# input-sequence.net
KiCad netlist of a schematic drawn in EAGLE
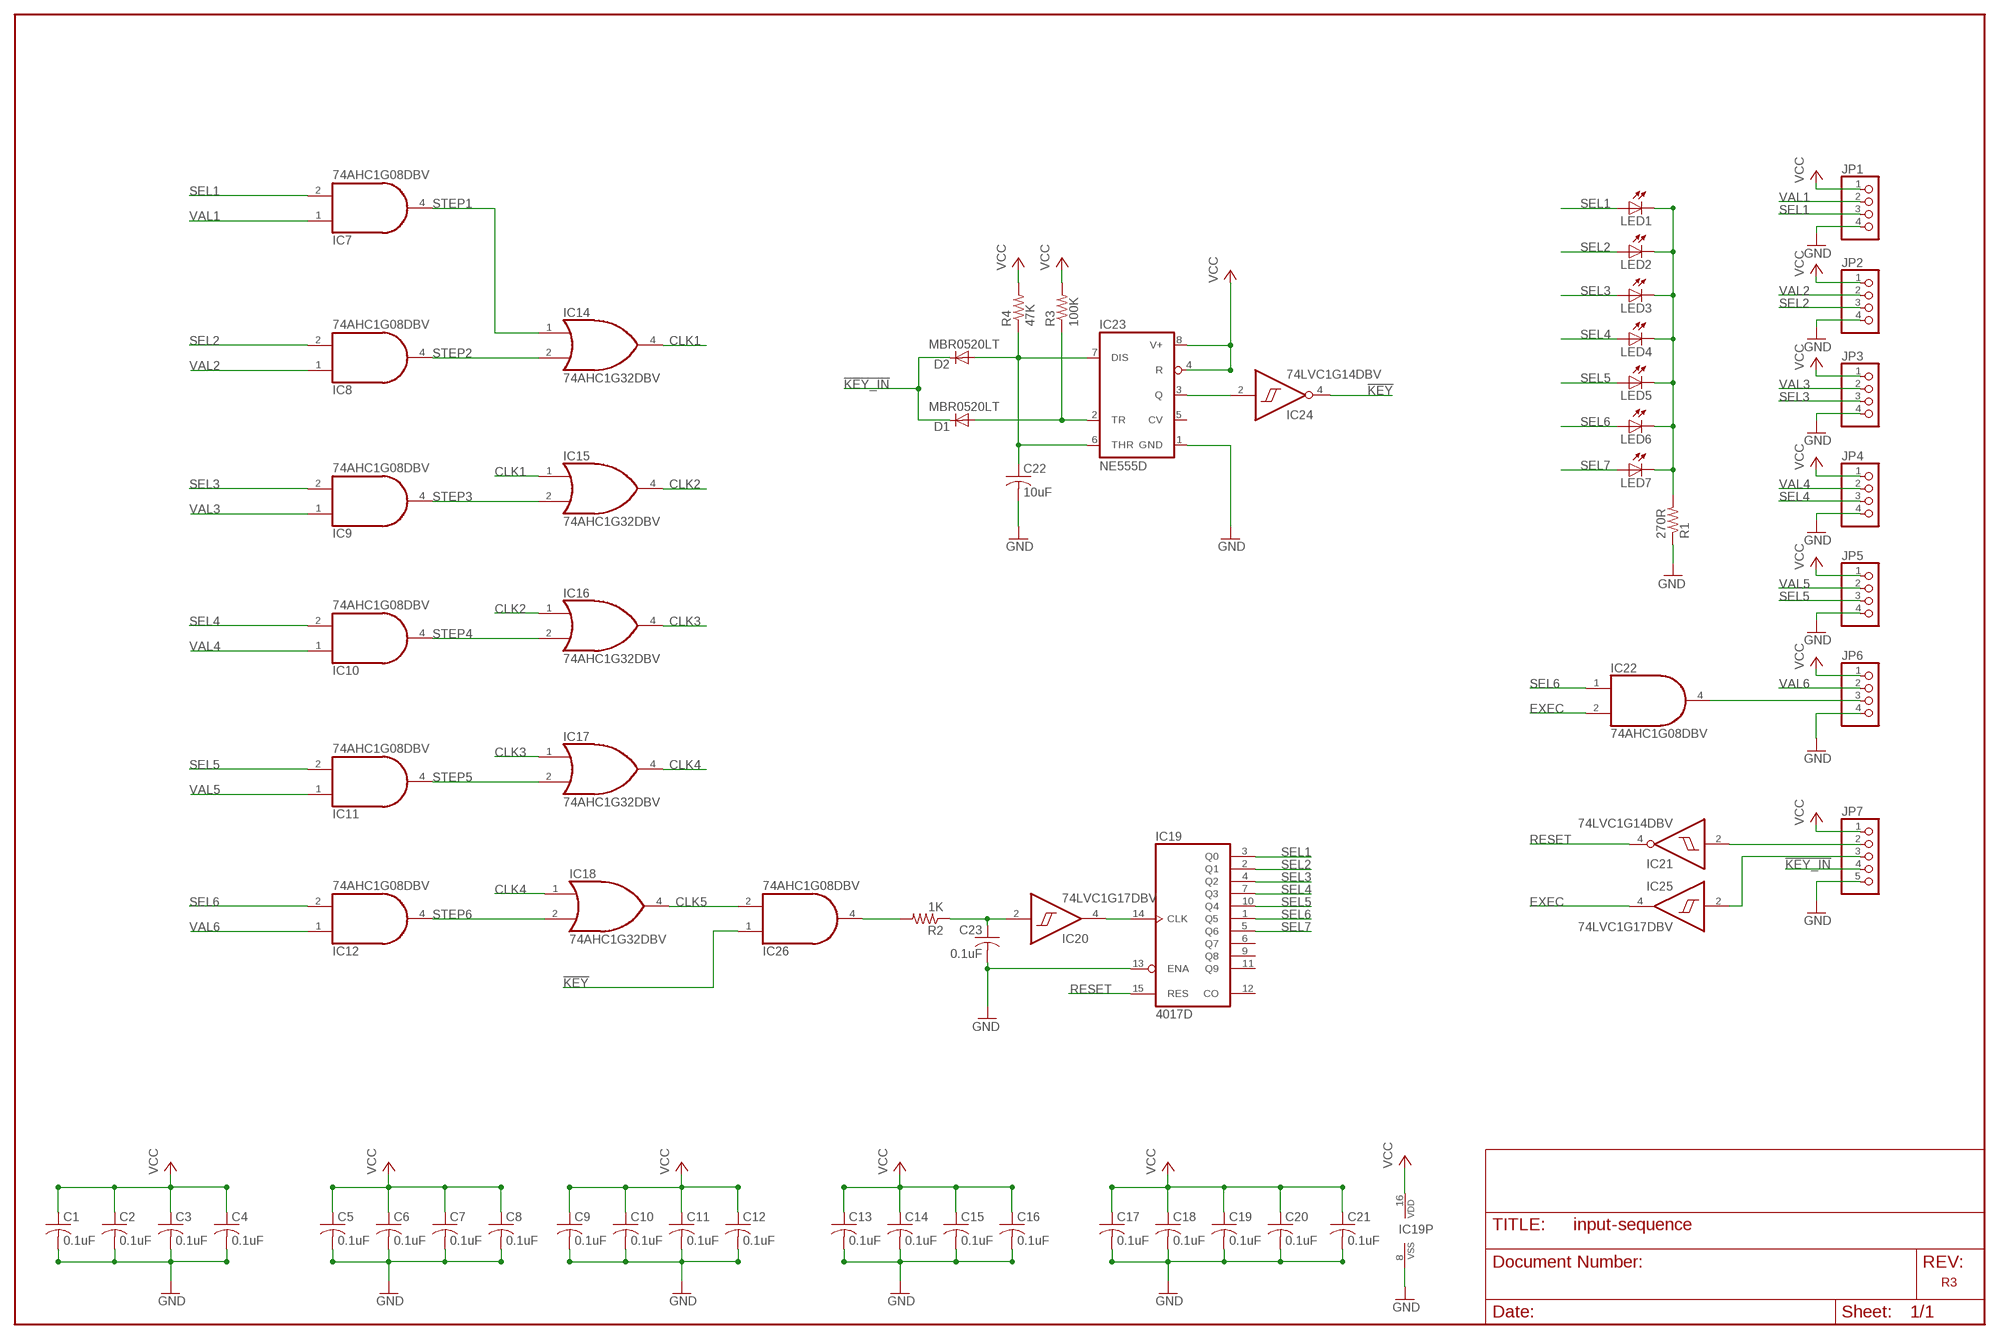
[diagram p0: schematic, sheet 1]

(export (version "E")
  (design (tool "Eeschema 10.0.6"))
  (components
    (comp (ref "C1")
      (value "0.1uF")
      (footprint "eagle-import:C0603")
      (libsource (lib "eagle-import") (part "C-USC0603"))
    )
    (comp (ref "C2")
      (value "0.1uF")
      (footprint "eagle-import:C0603")
      (libsource (lib "eagle-import") (part "C-USC0603"))
    )
    (comp (ref "C3")
      (value "0.1uF")
      (footprint "eagle-import:C0603")
      (libsource (lib "eagle-import") (part "C-USC0603"))
    )
    (comp (ref "C4")
      (value "0.1uF")
      (footprint "eagle-import:C0603")
      (libsource (lib "eagle-import") (part "C-USC0603"))
    )
    (comp (ref "C5")
      (value "0.1uF")
      (footprint "eagle-import:C0603")
      (libsource (lib "eagle-import") (part "C-USC0603"))
    )
    (comp (ref "C6")
      (value "0.1uF")
      (footprint "eagle-import:C0603")
      (libsource (lib "eagle-import") (part "C-USC0603"))
    )
    (comp (ref "C7")
      (value "0.1uF")
      (footprint "eagle-import:C0603")
      (libsource (lib "eagle-import") (part "C-USC0603"))
    )
    (comp (ref "C8")
      (value "0.1uF")
      (footprint "eagle-import:C0603")
      (libsource (lib "eagle-import") (part "C-USC0603"))
    )
    (comp (ref "C9")
      (value "0.1uF")
      (footprint "eagle-import:C0603")
      (libsource (lib "eagle-import") (part "C-USC0603"))
    )
    (comp (ref "C10")
      (value "0.1uF")
      (footprint "eagle-import:C0603")
      (libsource (lib "eagle-import") (part "C-USC0603"))
    )
    (comp (ref "C11")
      (value "0.1uF")
      (footprint "eagle-import:C0603")
      (libsource (lib "eagle-import") (part "C-USC0603"))
    )
    (comp (ref "C12")
      (value "0.1uF")
      (footprint "eagle-import:C0603")
      (libsource (lib "eagle-import") (part "C-USC0603"))
    )
    (comp (ref "C13")
      (value "0.1uF")
      (footprint "eagle-import:C0603")
      (libsource (lib "eagle-import") (part "C-USC0603"))
    )
    (comp (ref "C14")
      (value "0.1uF")
      (footprint "eagle-import:C0603")
      (libsource (lib "eagle-import") (part "C-USC0603"))
    )
    (comp (ref "C15")
      (value "0.1uF")
      (footprint "eagle-import:C0603")
      (libsource (lib "eagle-import") (part "C-USC0603"))
    )
    (comp (ref "C16")
      (value "0.1uF")
      (footprint "eagle-import:C0603")
      (libsource (lib "eagle-import") (part "C-USC0603"))
    )
    (comp (ref "C17")
      (value "0.1uF")
      (footprint "eagle-import:C0603")
      (libsource (lib "eagle-import") (part "C-USC0603"))
    )
    (comp (ref "C18")
      (value "0.1uF")
      (footprint "eagle-import:C0603")
      (libsource (lib "eagle-import") (part "C-USC0603"))
    )
    (comp (ref "C19")
      (value "0.1uF")
      (footprint "eagle-import:C0603")
      (libsource (lib "eagle-import") (part "C-USC0603"))
    )
    (comp (ref "C20")
      (value "0.1uF")
      (footprint "eagle-import:C0603")
      (libsource (lib "eagle-import") (part "C-USC0603"))
    )
    (comp (ref "C21")
      (value "0.1uF")
      (footprint "eagle-import:C0603")
      (libsource (lib "eagle-import") (part "C-USC0603"))
    )
    (comp (ref "C22")
      (value "10uF")
      (footprint "eagle-import:C0805")
      (libsource (lib "eagle-import") (part "C-USC0805"))
    )
    (comp (ref "C23")
      (value "0.1uF")
      (footprint "eagle-import:C0603")
      (libsource (lib "eagle-import") (part "C-USC0603"))
    )
    (comp (ref "D1")
      (value "MBR0520LT")
      (footprint "eagle-import:SOD123")
      (libsource (lib "eagle-import") (part "MBR0520LT"))
    )
    (comp (ref "D2")
      (value "MBR0520LT")
      (footprint "eagle-import:SOD123")
      (libsource (lib "eagle-import") (part "MBR0520LT"))
    )
    (comp (ref "IC7")
      (value "74AHC1G08DBV")
      (footprint "eagle-import:SOT23-5")
      (libsource (lib "eagle-import") (part "741G08DBVAHC"))
    )
    (comp (ref "IC8")
      (value "74AHC1G08DBV")
      (footprint "eagle-import:SOT23-5")
      (libsource (lib "eagle-import") (part "741G08DBVAHC"))
    )
    (comp (ref "IC9")
      (value "74AHC1G08DBV")
      (footprint "eagle-import:SOT23-5")
      (libsource (lib "eagle-import") (part "741G08DBVAHC"))
    )
    (comp (ref "IC10")
      (value "74AHC1G08DBV")
      (footprint "eagle-import:SOT23-5")
      (libsource (lib "eagle-import") (part "741G08DBVAHC"))
    )
    (comp (ref "IC11")
      (value "74AHC1G08DBV")
      (footprint "eagle-import:SOT23-5")
      (libsource (lib "eagle-import") (part "741G08DBVAHC"))
    )
    (comp (ref "IC12")
      (value "74AHC1G08DBV")
      (footprint "eagle-import:SOT23-5")
      (libsource (lib "eagle-import") (part "741G08DBVAHC"))
    )
    (comp (ref "IC14")
      (value "74AHC1G32DBV")
      (footprint "eagle-import:SOT23-5")
      (libsource (lib "eagle-import") (part "741G32DBVAHC"))
    )
    (comp (ref "IC15")
      (value "74AHC1G32DBV")
      (footprint "eagle-import:SOT23-5")
      (libsource (lib "eagle-import") (part "741G32DBVAHC"))
    )
    (comp (ref "IC16")
      (value "74AHC1G32DBV")
      (footprint "eagle-import:SOT23-5")
      (libsource (lib "eagle-import") (part "741G32DBVAHC"))
    )
    (comp (ref "IC17")
      (value "74AHC1G32DBV")
      (footprint "eagle-import:SOT23-5")
      (libsource (lib "eagle-import") (part "741G32DBVAHC"))
    )
    (comp (ref "IC18")
      (value "74AHC1G32DBV")
      (footprint "eagle-import:SOT23-5")
      (libsource (lib "eagle-import") (part "741G32DBVAHC"))
    )
    (comp (ref "IC19")
      (value "4017D")
      (footprint "eagle-import:SO16")
      (libsource (lib "eagle-import") (part "4017D"))
    )
    (comp (ref "IC20")
      (value "74LVC1G17DBV")
      (footprint "eagle-import:SOT23-5")
      (libsource (lib "eagle-import") (part "741G17DBVLVC"))
    )
    (comp (ref "IC21")
      (value "74LVC1G14DBV")
      (footprint "eagle-import:SOT23-5")
      (libsource (lib "eagle-import") (part "741G14DBVLVC"))
    )
    (comp (ref "IC22")
      (value "74AHC1G08DBV")
      (footprint "eagle-import:SOT23-5")
      (libsource (lib "eagle-import") (part "741G08DBVAHC"))
    )
    (comp (ref "IC23")
      (value "NE555D")
      (footprint "eagle-import:SO08")
      (libsource (lib "eagle-import") (part "555DNE"))
    )
    (comp (ref "IC24")
      (value "74LVC1G14DBV")
      (footprint "eagle-import:SOT23-5")
      (libsource (lib "eagle-import") (part "741G14DBVLVC"))
    )
    (comp (ref "IC25")
      (value "74LVC1G17DBV")
      (footprint "eagle-import:SOT23-5")
      (libsource (lib "eagle-import") (part "741G17DBVLVC"))
    )
    (comp (ref "IC26")
      (value "74AHC1G08DBV")
      (footprint "eagle-import:SOT23-5")
      (libsource (lib "eagle-import") (part "741G08DBVAHC"))
    )
    (comp (ref "JP1")
      (value "PINHD-1X4")
      (footprint "eagle-import:1X04")
      (libsource (lib "eagle-import") (part "PINHD-1X4"))
    )
    (comp (ref "JP2")
      (value "PINHD-1X4")
      (footprint "eagle-import:1X04")
      (libsource (lib "eagle-import") (part "PINHD-1X4"))
    )
    (comp (ref "JP3")
      (value "PINHD-1X4")
      (footprint "eagle-import:1X04")
      (libsource (lib "eagle-import") (part "PINHD-1X4"))
    )
    (comp (ref "JP4")
      (value "PINHD-1X4")
      (footprint "eagle-import:1X04")
      (libsource (lib "eagle-import") (part "PINHD-1X4"))
    )
    (comp (ref "JP5")
      (value "PINHD-1X4")
      (footprint "eagle-import:1X04")
      (libsource (lib "eagle-import") (part "PINHD-1X4"))
    )
    (comp (ref "JP6")
      (value "PINHD-1X4")
      (footprint "eagle-import:1X04")
      (libsource (lib "eagle-import") (part "PINHD-1X4"))
    )
    (comp (ref "JP7")
      (value "PINHD-1X5")
      (footprint "eagle-import:1X05")
      (libsource (lib "eagle-import") (part "PINHD-1X5"))
    )
    (comp (ref "LED1")
      (value "RED")
      (footprint "eagle-import:CHIP-LED0805")
      (libsource (lib "eagle-import") (part "LEDCHIP-LED0805"))
    )
    (comp (ref "LED2")
      (value "RED")
      (footprint "eagle-import:CHIP-LED0805")
      (libsource (lib "eagle-import") (part "LEDCHIP-LED0805"))
    )
    (comp (ref "LED3")
      (value "RED")
      (footprint "eagle-import:CHIP-LED0805")
      (libsource (lib "eagle-import") (part "LEDCHIP-LED0805"))
    )
    (comp (ref "LED4")
      (value "RED")
      (footprint "eagle-import:CHIP-LED0805")
      (libsource (lib "eagle-import") (part "LEDCHIP-LED0805"))
    )
    (comp (ref "LED5")
      (value "RED")
      (footprint "eagle-import:CHIP-LED0805")
      (libsource (lib "eagle-import") (part "LEDCHIP-LED0805"))
    )
    (comp (ref "LED6")
      (value "RED")
      (footprint "eagle-import:CHIP-LED0805")
      (libsource (lib "eagle-import") (part "LEDCHIP-LED0805"))
    )
    (comp (ref "LED7")
      (value "RED")
      (footprint "eagle-import:CHIP-LED0805")
      (libsource (lib "eagle-import") (part "LEDCHIP-LED0805"))
    )
    (comp (ref "R1")
      (value "270R")
      (footprint "eagle-import:R0805")
      (libsource (lib "eagle-import") (part "R-US_R0805"))
    )
    (comp (ref "R2")
      (value "1K")
      (footprint "eagle-import:R0805")
      (libsource (lib "eagle-import") (part "R-US_R0805"))
    )
    (comp (ref "R3")
      (value "100K")
      (footprint "eagle-import:R0805")
      (libsource (lib "eagle-import") (part "R-US_R0805"))
    )
    (comp (ref "R4")
      (value "47K")
      (footprint "eagle-import:R0805")
      (libsource (lib "eagle-import") (part "R-US_R0805"))
    )
  )
  (nets
    (net (code "1") (name "/CLK1") (class "Default")
      (node (ref "IC14") (pin "4") (pinfunction "O_4") (pintype "output"))
      (node (ref "IC15") (pin "1") (pinfunction "I0_1") (pintype "input"))
    )
    (net (code "2") (name "/CLK2") (class "Default")
      (node (ref "IC15") (pin "4") (pinfunction "O_4") (pintype "output"))
      (node (ref "IC16") (pin "1") (pinfunction "I0_1") (pintype "input"))
    )
    (net (code "3") (name "/CLK3") (class "Default")
      (node (ref "IC16") (pin "4") (pinfunction "O_4") (pintype "output"))
      (node (ref "IC17") (pin "1") (pinfunction "I0_1") (pintype "input"))
    )
    (net (code "4") (name "/CLK4") (class "Default")
      (node (ref "IC17") (pin "4") (pinfunction "O_4") (pintype "output"))
      (node (ref "IC18") (pin "1") (pinfunction "I0_1") (pintype "input"))
    )
    (net (code "5") (name "/CLK5") (class "Default")
      (node (ref "IC18") (pin "4") (pinfunction "O_4") (pintype "output"))
      (node (ref "IC26") (pin "2") (pinfunction "I1_2") (pintype "input"))
    )
    (net (code "6") (name "/EXEC") (class "Default")
      (node (ref "IC22") (pin "2") (pinfunction "I1_2") (pintype "input"))
      (node (ref "IC25") (pin "4") (pinfunction "O_4") (pintype "output"))
    )
    (net (code "7") (name "/RESET") (class "Default")
      (node (ref "IC19") (pin "15") (pinfunction "RES_15") (pintype "input"))
      (node (ref "IC21") (pin "4") (pinfunction "O_4") (pintype "output"))
    )
    (net (code "8") (name "/SEL1") (class "Default")
      (node (ref "IC19") (pin "3") (pinfunction "Q0_3") (pintype "output"))
      (node (ref "IC7") (pin "2") (pinfunction "I1_2") (pintype "input"))
      (node (ref "JP1") (pin "3") (pinfunction "3_3") (pintype "passive"))
      (node (ref "LED1") (pin "A") (pinfunction "A_A") (pintype "passive"))
    )
    (net (code "9") (name "/SEL2") (class "Default")
      (node (ref "IC19") (pin "2") (pinfunction "Q1_2") (pintype "output"))
      (node (ref "IC8") (pin "2") (pinfunction "I1_2") (pintype "input"))
      (node (ref "JP2") (pin "3") (pinfunction "3_3") (pintype "passive"))
      (node (ref "LED2") (pin "A") (pinfunction "A_A") (pintype "passive"))
    )
    (net (code "10") (name "/SEL3") (class "Default")
      (node (ref "IC19") (pin "4") (pinfunction "Q2_4") (pintype "output"))
      (node (ref "IC9") (pin "2") (pinfunction "I1_2") (pintype "input"))
      (node (ref "JP3") (pin "3") (pinfunction "3_3") (pintype "passive"))
      (node (ref "LED3") (pin "A") (pinfunction "A_A") (pintype "passive"))
    )
    (net (code "11") (name "/SEL4") (class "Default")
      (node (ref "IC10") (pin "2") (pinfunction "I1_2") (pintype "input"))
      (node (ref "IC19") (pin "7") (pinfunction "Q3_7") (pintype "output"))
      (node (ref "JP4") (pin "3") (pinfunction "3_3") (pintype "passive"))
      (node (ref "LED4") (pin "A") (pinfunction "A_A") (pintype "passive"))
    )
    (net (code "12") (name "/SEL5") (class "Default")
      (node (ref "IC11") (pin "2") (pinfunction "I1_2") (pintype "input"))
      (node (ref "IC19") (pin "10") (pinfunction "Q4_10") (pintype "output"))
      (node (ref "JP5") (pin "3") (pinfunction "3_3") (pintype "passive"))
      (node (ref "LED5") (pin "A") (pinfunction "A_A") (pintype "passive"))
    )
    (net (code "13") (name "/SEL6") (class "Default")
      (node (ref "IC12") (pin "2") (pinfunction "I1_2") (pintype "input"))
      (node (ref "IC19") (pin "1") (pinfunction "Q5_1") (pintype "output"))
      (node (ref "IC22") (pin "1") (pinfunction "I0_1") (pintype "input"))
      (node (ref "LED6") (pin "A") (pinfunction "A_A") (pintype "passive"))
    )
    (net (code "14") (name "/SEL7") (class "Default")
      (node (ref "IC19") (pin "5") (pinfunction "Q6_5") (pintype "output"))
      (node (ref "LED7") (pin "A") (pinfunction "A_A") (pintype "passive"))
    )
    (net (code "15") (name "/STEP1") (class "Default")
      (node (ref "IC14") (pin "1") (pinfunction "I0_1") (pintype "input"))
      (node (ref "IC7") (pin "4") (pinfunction "O_4") (pintype "output"))
    )
    (net (code "16") (name "/STEP2") (class "Default")
      (node (ref "IC14") (pin "2") (pinfunction "I1_2") (pintype "input"))
      (node (ref "IC8") (pin "4") (pinfunction "O_4") (pintype "output"))
    )
    (net (code "17") (name "/STEP3") (class "Default")
      (node (ref "IC15") (pin "2") (pinfunction "I1_2") (pintype "input"))
      (node (ref "IC9") (pin "4") (pinfunction "O_4") (pintype "output"))
    )
    (net (code "18") (name "/STEP4") (class "Default")
      (node (ref "IC10") (pin "4") (pinfunction "O_4") (pintype "output"))
      (node (ref "IC16") (pin "2") (pinfunction "I1_2") (pintype "input"))
    )
    (net (code "19") (name "/STEP5") (class "Default")
      (node (ref "IC11") (pin "4") (pinfunction "O_4") (pintype "output"))
      (node (ref "IC17") (pin "2") (pinfunction "I1_2") (pintype "input"))
    )
    (net (code "20") (name "/STEP6") (class "Default")
      (node (ref "IC12") (pin "4") (pinfunction "O_4") (pintype "output"))
      (node (ref "IC18") (pin "2") (pinfunction "I1_2") (pintype "input"))
    )
    (net (code "21") (name "/VAL1") (class "Default")
      (node (ref "IC7") (pin "1") (pinfunction "I0_1") (pintype "input"))
      (node (ref "JP1") (pin "2") (pinfunction "2_2") (pintype "passive"))
    )
    (net (code "22") (name "/VAL2") (class "Default")
      (node (ref "IC8") (pin "1") (pinfunction "I0_1") (pintype "input"))
      (node (ref "JP2") (pin "2") (pinfunction "2_2") (pintype "passive"))
    )
    (net (code "23") (name "/VAL3") (class "Default")
      (node (ref "IC9") (pin "1") (pinfunction "I0_1") (pintype "input"))
      (node (ref "JP3") (pin "2") (pinfunction "2_2") (pintype "passive"))
    )
    (net (code "24") (name "/VAL4") (class "Default")
      (node (ref "IC10") (pin "1") (pinfunction "I0_1") (pintype "input"))
      (node (ref "JP4") (pin "2") (pinfunction "2_2") (pintype "passive"))
    )
    (net (code "25") (name "/VAL5") (class "Default")
      (node (ref "IC11") (pin "1") (pinfunction "I0_1") (pintype "input"))
      (node (ref "JP5") (pin "2") (pinfunction "2_2") (pintype "passive"))
    )
    (net (code "26") (name "/VAL6") (class "Default")
      (node (ref "IC12") (pin "1") (pinfunction "I0_1") (pintype "input"))
      (node (ref "JP6") (pin "2") (pinfunction "2_2") (pintype "passive"))
    )
    (net (code "27") (name "/~{KEY_IN}") (class "Default")
      (node (ref "D1") (pin "C") (pinfunction "C_C") (pintype "passive"))
      (node (ref "D2") (pin "C") (pinfunction "C_C") (pintype "passive"))
      (node (ref "JP7") (pin "4") (pinfunction "4_4") (pintype "passive"))
    )
    (net (code "28") (name "/~{KEY}") (class "Default")
      (node (ref "IC24") (pin "4") (pinfunction "O_4") (pintype "output"))
      (node (ref "IC26") (pin "1") (pinfunction "I0_1") (pintype "input"))
    )
    (net (code "29") (name "GND") (class "Default")
      (node (ref "C1") (pin "2") (pinfunction "2_2") (pintype "passive"))
      (node (ref "C10") (pin "2") (pinfunction "2_2") (pintype "passive"))
      (node (ref "C11") (pin "2") (pinfunction "2_2") (pintype "passive"))
      (node (ref "C12") (pin "2") (pinfunction "2_2") (pintype "passive"))
      (node (ref "C13") (pin "2") (pinfunction "2_2") (pintype "passive"))
      (node (ref "C14") (pin "2") (pinfunction "2_2") (pintype "passive"))
      (node (ref "C15") (pin "2") (pinfunction "2_2") (pintype "passive"))
      (node (ref "C16") (pin "2") (pinfunction "2_2") (pintype "passive"))
      (node (ref "C17") (pin "2") (pinfunction "2_2") (pintype "passive"))
      (node (ref "C18") (pin "2") (pinfunction "2_2") (pintype "passive"))
      (node (ref "C19") (pin "2") (pinfunction "2_2") (pintype "passive"))
      (node (ref "C2") (pin "2") (pinfunction "2_2") (pintype "passive"))
      (node (ref "C20") (pin "2") (pinfunction "2_2") (pintype "passive"))
      (node (ref "C21") (pin "2") (pinfunction "2_2") (pintype "passive"))
      (node (ref "C22") (pin "2") (pinfunction "2_2") (pintype "passive"))
      (node (ref "C23") (pin "2") (pinfunction "2_2") (pintype "passive"))
      (node (ref "C3") (pin "2") (pinfunction "2_2") (pintype "passive"))
      (node (ref "C4") (pin "2") (pinfunction "2_2") (pintype "passive"))
      (node (ref "C5") (pin "2") (pinfunction "2_2") (pintype "passive"))
      (node (ref "C6") (pin "2") (pinfunction "2_2") (pintype "passive"))
      (node (ref "C7") (pin "2") (pinfunction "2_2") (pintype "passive"))
      (node (ref "C8") (pin "2") (pinfunction "2_2") (pintype "passive"))
      (node (ref "C9") (pin "2") (pinfunction "2_2") (pintype "passive"))
      (node (ref "IC19") (pin "13") (pinfunction "ENA_13") (pintype "input"))
      (node (ref "IC19") (pin "8") (pinfunction "VSS_8") (pintype "power_in"))
      (node (ref "IC23") (pin "1") (pinfunction "GND_1") (pintype "power_in"))
      (node (ref "JP1") (pin "4") (pinfunction "4_4") (pintype "passive"))
      (node (ref "JP2") (pin "4") (pinfunction "4_4") (pintype "passive"))
      (node (ref "JP3") (pin "4") (pinfunction "4_4") (pintype "passive"))
      (node (ref "JP4") (pin "4") (pinfunction "4_4") (pintype "passive"))
      (node (ref "JP5") (pin "4") (pinfunction "4_4") (pintype "passive"))
      (node (ref "JP6") (pin "4") (pinfunction "4_4") (pintype "passive"))
      (node (ref "JP7") (pin "5") (pinfunction "5_5") (pintype "passive"))
      (node (ref "R1") (pin "1") (pinfunction "1_1") (pintype "passive"))
    )
    (net (code "30") (name "Net-(IC19A-CLK)") (class "Default")
      (node (ref "IC19") (pin "14") (pinfunction "CLK_14") (pintype "input"))
      (node (ref "IC20") (pin "4") (pinfunction "O_4") (pintype "output"))
    )
    (net (code "31") (name "Net-(IC20A-I)") (class "Default")
      (node (ref "C23") (pin "1") (pinfunction "1_1") (pintype "passive"))
      (node (ref "IC20") (pin "2") (pinfunction "I_2") (pintype "input"))
      (node (ref "R2") (pin "1") (pinfunction "1_1") (pintype "passive"))
    )
    (net (code "32") (name "Net-(IC21A-I)") (class "Default")
      (node (ref "IC21") (pin "2") (pinfunction "I_2") (pintype "input"))
      (node (ref "JP7") (pin "2") (pinfunction "2_2") (pintype "passive"))
    )
    (net (code "33") (name "Net-(IC22A-O)") (class "Default")
      (node (ref "IC22") (pin "4") (pinfunction "O_4") (pintype "output"))
      (node (ref "JP6") (pin "3") (pinfunction "3_3") (pintype "passive"))
    )
    (net (code "34") (name "Net-(IC23-DIS)") (class "Default")
      (node (ref "C22") (pin "1") (pinfunction "1_1") (pintype "passive"))
      (node (ref "D2") (pin "A") (pinfunction "A_A") (pintype "passive"))
      (node (ref "IC23") (pin "6") (pinfunction "THR_6") (pintype "input"))
      (node (ref "IC23") (pin "7") (pinfunction "DIS_7") (pintype "input"))
      (node (ref "R4") (pin "1") (pinfunction "1_1") (pintype "passive"))
    )
    (net (code "35") (name "Net-(IC23-Q)") (class "Default")
      (node (ref "IC23") (pin "3") (pinfunction "Q_3") (pintype "output"))
      (node (ref "IC24") (pin "2") (pinfunction "I_2") (pintype "input"))
    )
    (net (code "36") (name "Net-(IC23-TR)") (class "Default")
      (node (ref "D1") (pin "A") (pinfunction "A_A") (pintype "passive"))
      (node (ref "IC23") (pin "2") (pinfunction "TR_2") (pintype "input"))
      (node (ref "R3") (pin "1") (pinfunction "1_1") (pintype "passive"))
    )
    (net (code "37") (name "Net-(IC25A-I)") (class "Default")
      (node (ref "IC25") (pin "2") (pinfunction "I_2") (pintype "input"))
      (node (ref "JP7") (pin "3") (pinfunction "3_3") (pintype "passive"))
    )
    (net (code "38") (name "Net-(IC26A-O)") (class "Default")
      (node (ref "IC26") (pin "4") (pinfunction "O_4") (pintype "output"))
      (node (ref "R2") (pin "2") (pinfunction "2_2") (pintype "passive"))
    )
    (net (code "39") (name "Net-(LED1-PadC)") (class "Default")
      (node (ref "LED1") (pin "C") (pinfunction "C_C") (pintype "passive"))
      (node (ref "LED2") (pin "C") (pinfunction "C_C") (pintype "passive"))
      (node (ref "LED3") (pin "C") (pinfunction "C_C") (pintype "passive"))
      (node (ref "LED4") (pin "C") (pinfunction "C_C") (pintype "passive"))
      (node (ref "LED5") (pin "C") (pinfunction "C_C") (pintype "passive"))
      (node (ref "LED6") (pin "C") (pinfunction "C_C") (pintype "passive"))
      (node (ref "LED7") (pin "C") (pinfunction "C_C") (pintype "passive"))
      (node (ref "R1") (pin "2") (pinfunction "2_2") (pintype "passive"))
    )
    (net (code "40") (name "VCC") (class "Default")
      (node (ref "C1") (pin "1") (pinfunction "1_1") (pintype "passive"))
      (node (ref "C10") (pin "1") (pinfunction "1_1") (pintype "passive"))
      (node (ref "C11") (pin "1") (pinfunction "1_1") (pintype "passive"))
      (node (ref "C12") (pin "1") (pinfunction "1_1") (pintype "passive"))
      (node (ref "C13") (pin "1") (pinfunction "1_1") (pintype "passive"))
      (node (ref "C14") (pin "1") (pinfunction "1_1") (pintype "passive"))
      (node (ref "C15") (pin "1") (pinfunction "1_1") (pintype "passive"))
      (node (ref "C16") (pin "1") (pinfunction "1_1") (pintype "passive"))
      (node (ref "C17") (pin "1") (pinfunction "1_1") (pintype "passive"))
      (node (ref "C18") (pin "1") (pinfunction "1_1") (pintype "passive"))
      (node (ref "C19") (pin "1") (pinfunction "1_1") (pintype "passive"))
      (node (ref "C2") (pin "1") (pinfunction "1_1") (pintype "passive"))
      (node (ref "C20") (pin "1") (pinfunction "1_1") (pintype "passive"))
      (node (ref "C21") (pin "1") (pinfunction "1_1") (pintype "passive"))
      (node (ref "C3") (pin "1") (pinfunction "1_1") (pintype "passive"))
      (node (ref "C4") (pin "1") (pinfunction "1_1") (pintype "passive"))
      (node (ref "C5") (pin "1") (pinfunction "1_1") (pintype "passive"))
      (node (ref "C6") (pin "1") (pinfunction "1_1") (pintype "passive"))
      (node (ref "C7") (pin "1") (pinfunction "1_1") (pintype "passive"))
      (node (ref "C8") (pin "1") (pinfunction "1_1") (pintype "passive"))
      (node (ref "C9") (pin "1") (pinfunction "1_1") (pintype "passive"))
      (node (ref "IC19") (pin "16") (pinfunction "VDD_16") (pintype "power_in"))
      (node (ref "IC23") (pin "4") (pinfunction "R_4") (pintype "input"))
      (node (ref "IC23") (pin "8") (pinfunction "V+_8") (pintype "power_in"))
      (node (ref "JP1") (pin "1") (pinfunction "1_1") (pintype "passive"))
      (node (ref "JP2") (pin "1") (pinfunction "1_1") (pintype "passive"))
      (node (ref "JP3") (pin "1") (pinfunction "1_1") (pintype "passive"))
      (node (ref "JP4") (pin "1") (pinfunction "1_1") (pintype "passive"))
      (node (ref "JP5") (pin "1") (pinfunction "1_1") (pintype "passive"))
      (node (ref "JP6") (pin "1") (pinfunction "1_1") (pintype "passive"))
      (node (ref "JP7") (pin "1") (pinfunction "1_1") (pintype "passive"))
      (node (ref "R3") (pin "2") (pinfunction "2_2") (pintype "passive"))
      (node (ref "R4") (pin "2") (pinfunction "2_2") (pintype "passive"))
    )
    (net (code "41") (name "unconnected-(IC19A-CO-Pad12)") (class "Default")
      (node (ref "IC19") (pin "12") (pinfunction "CO_12") (pintype "output"))
    )
    (net (code "42") (name "unconnected-(IC19A-Q7-Pad6)") (class "Default")
      (node (ref "IC19") (pin "6") (pinfunction "Q7_6") (pintype "output"))
    )
    (net (code "43") (name "unconnected-(IC19A-Q8-Pad9)") (class "Default")
      (node (ref "IC19") (pin "9") (pinfunction "Q8_9") (pintype "output"))
    )
    (net (code "44") (name "unconnected-(IC19A-Q9-Pad11)") (class "Default")
      (node (ref "IC19") (pin "11") (pinfunction "Q9_11") (pintype "output"))
    )
    (net (code "45") (name "unconnected-(IC23-CV-Pad5)") (class "Default")
      (node (ref "IC23") (pin "5") (pinfunction "CV_5") (pintype "input"))
    )
  )
)
